# HAT_controller.net
KiCad netlist of a schematic drawn in Altium Designer
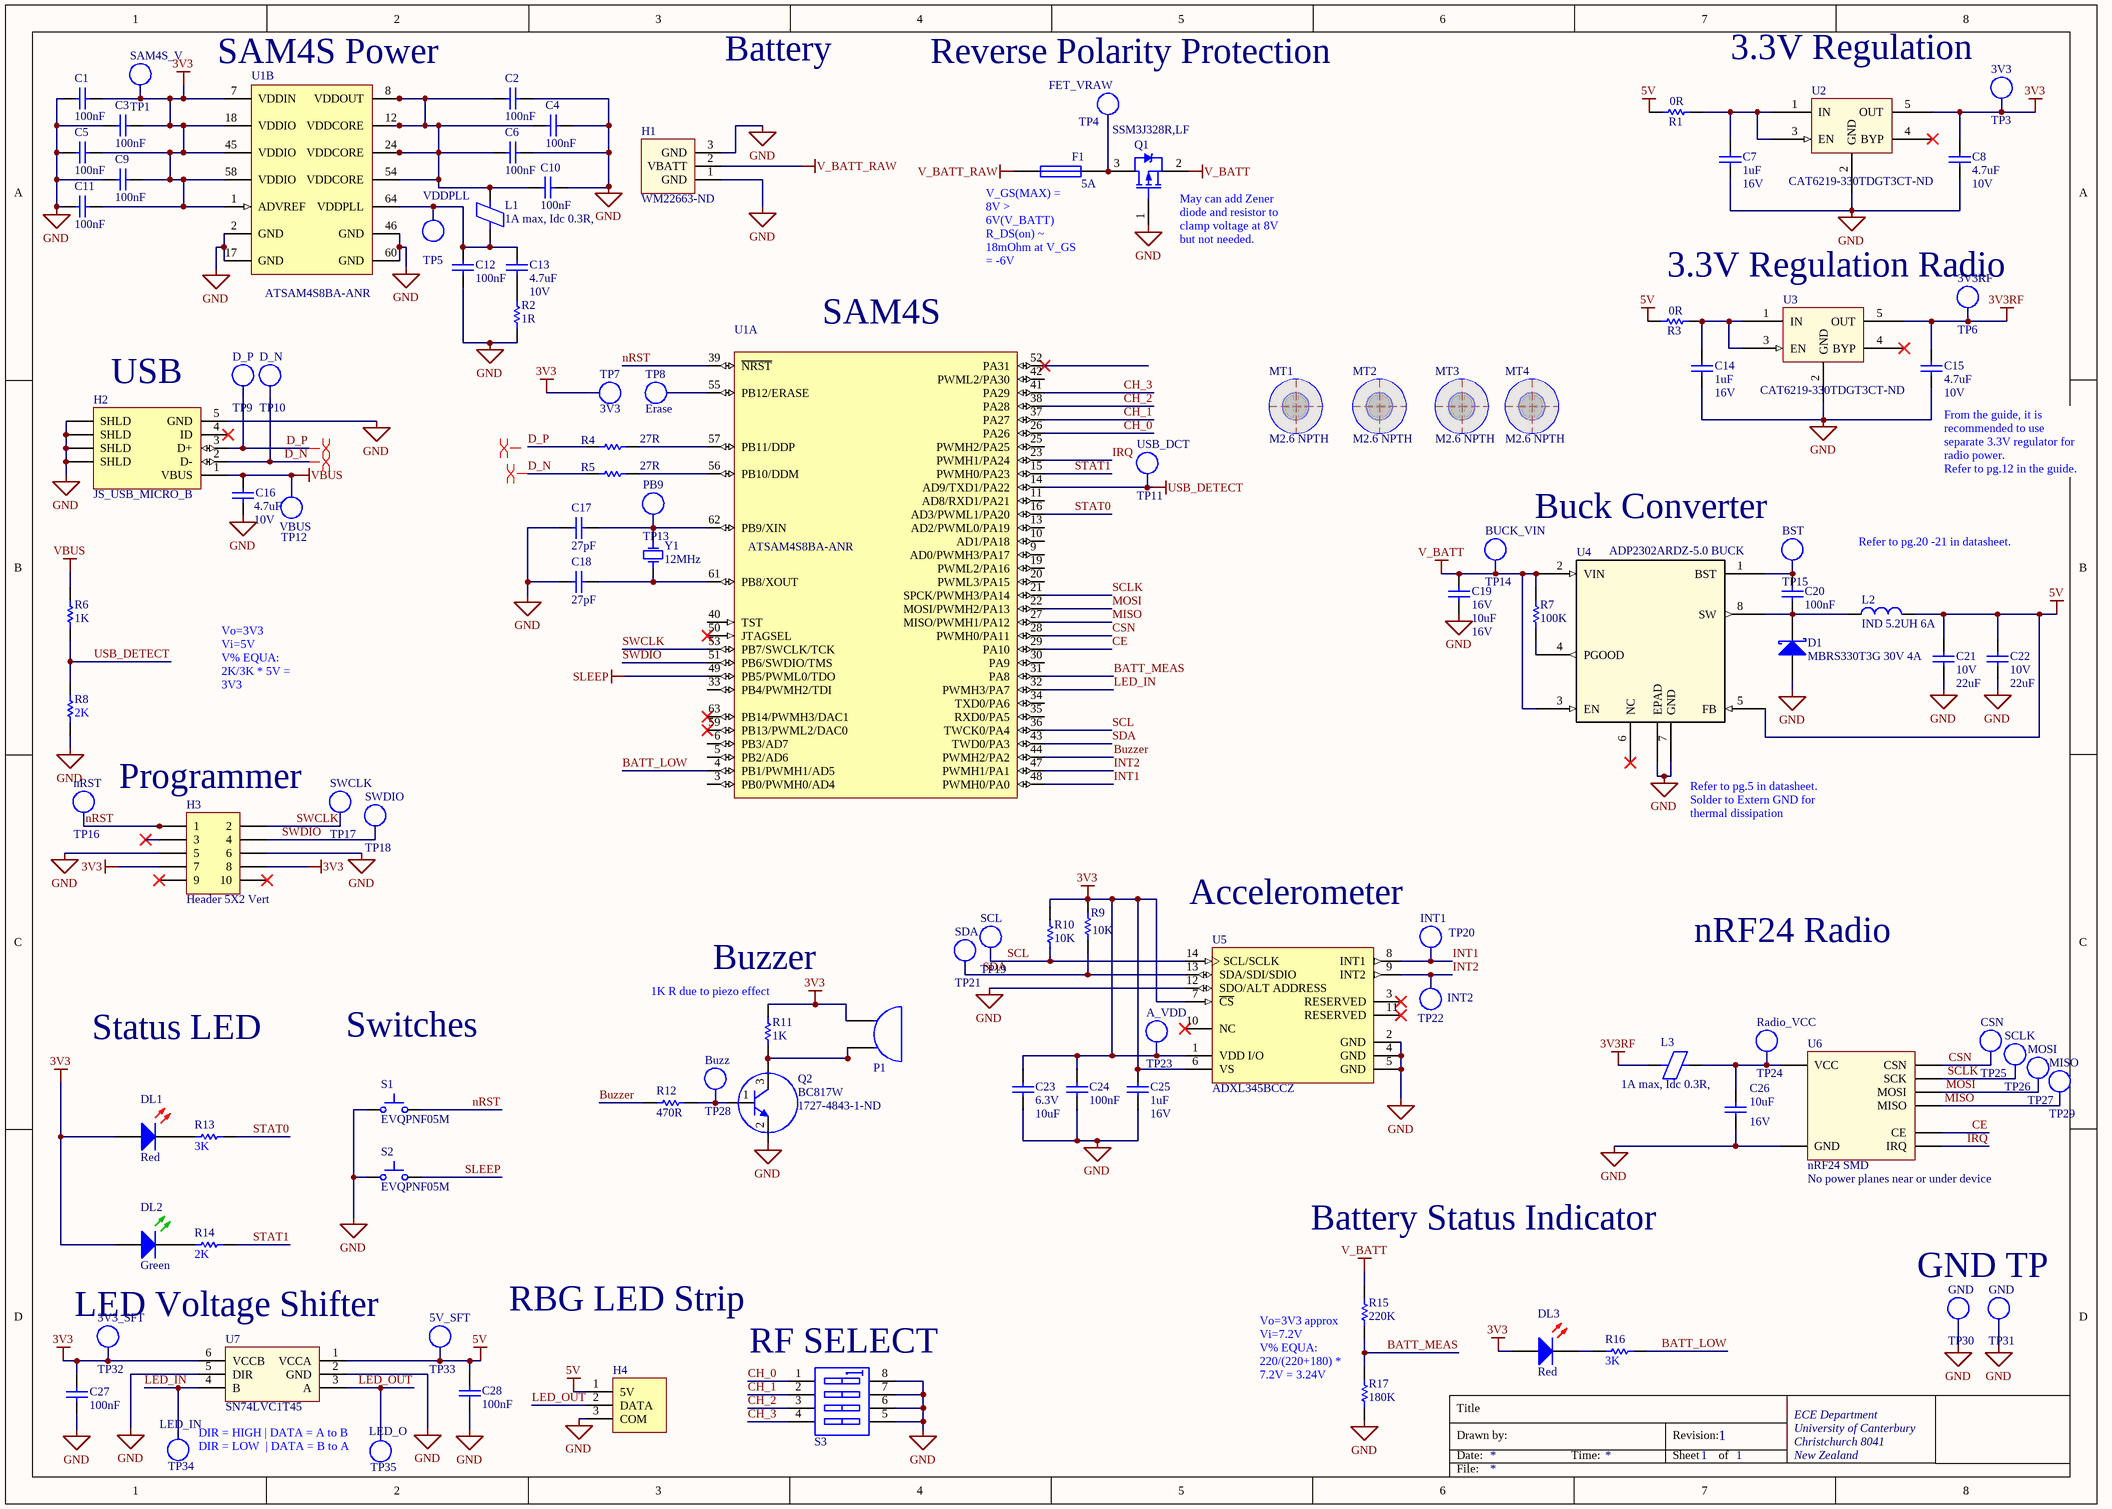
[diagram p0: HAT_controller.SchDoc]

(export (version "E")
  (design (tool "Eeschema 10.0.6"))
  (components
    (comp (ref "C1")
      (value "100nF")
      (footprint "CAPC1608L")
      (description "CAP CER 100nF X7R +-10% 50V 0603")
      (libsource (lib "ECE_ComponentsAD23") (part "CC_100nF_0603"))
    )
    (comp (ref "C2")
      (value "100nF")
      (footprint "CAPC1608L")
      (description "CAP CER 100nF X7R +-10% 50V 0603")
      (libsource (lib "ECE_ComponentsAD23") (part "CC_100nF_0603"))
    )
    (comp (ref "C3")
      (value "100nF")
      (footprint "CAPC1608L")
      (description "CAP CER 100nF X7R +-10% 50V 0603")
      (libsource (lib "ECE_ComponentsAD23") (part "CC_100nF_0603"))
    )
    (comp (ref "C4")
      (value "100nF")
      (footprint "CAPC1608L")
      (description "CAP CER 100nF X7R +-10% 50V 0603")
      (libsource (lib "ECE_ComponentsAD23") (part "CC_100nF_0603"))
    )
    (comp (ref "C5")
      (value "100nF")
      (footprint "CAPC1608L")
      (description "CAP CER 100nF X7R +-10% 50V 0603")
      (libsource (lib "ECE_ComponentsAD23") (part "CC_100nF_0603"))
    )
    (comp (ref "C6")
      (value "100nF")
      (footprint "CAPC1608L")
      (description "CAP CER 100nF X7R +-10% 50V 0603")
      (libsource (lib "ECE_ComponentsAD23") (part "CC_100nF_0603"))
    )
    (comp (ref "C7")
      (value "1uF")
      (footprint "CAPC1608L")
      (description "CAP CER 1uF Y5V -20% +80% 16V 0603")
      (fields (field (name "MAX VOLTAGE") "16V"))
      (libsource (lib "ECE_ComponentsAD23") (part "CC_1uF_0603"))
    )
    (comp (ref "C8")
      (value "4.7uF")
      (footprint "CAPC1608N")
      (description "CAP CER 4.7uF X5R +-20%  10V 0603")
      (fields (field (name "MAX VOLTAGE") "10V"))
      (libsource (lib "ECE_ComponentsAD23") (part "CC_4.7uF_0603"))
    )
    (comp (ref "C9")
      (value "100nF")
      (footprint "CAPC1608L")
      (description "CAP CER 100nF X7R +-10% 50V 0603")
      (libsource (lib "ECE_ComponentsAD23") (part "CC_100nF_0603"))
    )
    (comp (ref "C10")
      (value "100nF")
      (footprint "CAPC1608L")
      (description "CAP CER 100nF X7R +-10% 50V 0603")
      (libsource (lib "ECE_ComponentsAD23") (part "CC_100nF_0603"))
    )
    (comp (ref "C11")
      (value "100nF")
      (footprint "CAPC1608L")
      (description "CAP CER 100nF X7R +-10% 50V 0603")
      (libsource (lib "ECE_ComponentsAD23") (part "CC_100nF_0603"))
    )
    (comp (ref "C12")
      (value "100nF")
      (footprint "CAPC1608L")
      (description "CAP CER 100nF X7R +-10% 50V 0603")
      (libsource (lib "ECE_ComponentsAD23") (part "CC_100nF_0603"))
    )
    (comp (ref "C13")
      (value "4.7uF")
      (footprint "CAPC1608N")
      (description "CAP CER 4.7uF X5R +-20%  10V 0603")
      (fields (field (name "MAX VOLTAGE") "10V"))
      (libsource (lib "ECE_ComponentsAD23") (part "CC_4.7uF_0603"))
    )
    (comp (ref "C14")
      (value "1uF")
      (footprint "CAPC1608L")
      (description "CAP CER 1uF Y5V -20% +80% 16V 0603")
      (fields (field (name "MAX VOLTAGE") "16V"))
      (libsource (lib "ECE_ComponentsAD23") (part "CC_1uF_0603"))
    )
    (comp (ref "C15")
      (value "4.7uF")
      (footprint "CAPC1608N")
      (description "CAP CER 4.7uF X5R +-20%  10V 0603")
      (fields (field (name "MAX VOLTAGE") "10V"))
      (libsource (lib "ECE_ComponentsAD23") (part "CC_4.7uF_0603"))
    )
    (comp (ref "C16")
      (value "4.7uF")
      (footprint "CAPC1608N")
      (description "CAP CER 4.7uF X5R +-20%  10V 0603")
      (fields (field (name "MAX VOLTAGE") "10V"))
      (libsource (lib "ECE_ComponentsAD23") (part "CC_4.7uF_0603"))
    )
    (comp (ref "C17")
      (value "27pF")
      (footprint "CAPC1608L")
      (description "CAP CER 27pF NPO/COG +-5% 50V 0603")
      (libsource (lib "ECE_ComponentsAD23") (part "CC_27pF_0603"))
    )
    (comp (ref "C18")
      (value "27pF")
      (footprint "CAPC1608L")
      (description "CAP CER 27pF NPO/COG +-5% 50V 0603")
      (libsource (lib "ECE_ComponentsAD23") (part "CC_27pF_0603"))
    )
    (comp (ref "C19")
      (value "10uF")
      (footprint "CAPC2012L")
      (description "CAP CER 10uF X5R 16V 0805")
      (fields
        (field (name "MANUFACTURER") "Samsung Electro-Mechanics")
        (field (name "MANUFACTURER PART NUMBER") "CL21A106KOQNNWE")
        (field (name "VOLTAGE - RATED") "16V")
        (field (name "MAX VOLTAGE") "16V")
      )
      (libsource (lib "ECE_ComponentsAD23") (part "CC_10uF_0805_16V"))
    )
    (comp (ref "C20")
      (value "100nF")
      (footprint "CAPC1608L")
      (description "CAP CER 100nF X7R +-10% 50V 0603")
      (libsource (lib "ECE_ComponentsAD23") (part "CC_100nF_0603"))
    )
    (comp (ref "C21")
      (value "22uF")
      (footprint "CAPC3216L")
      (description "CAP CER 22uF Y5V -20% +80% 10V 1206")
      (fields (field (name "MAX VOLTAGE") "10V"))
      (libsource (lib "ECE_ComponentsAD23") (part "CC_22uF_1206"))
    )
    (comp (ref "C22")
      (value "22uF")
      (footprint "CAPC3216L")
      (description "CAP CER 22uF Y5V -20% +80% 10V 1206")
      (fields (field (name "MAX VOLTAGE") "10V"))
      (libsource (lib "ECE_ComponentsAD23") (part "CC_22uF_1206"))
    )
    (comp (ref "C23")
      (value "10uF")
      (footprint "CAPC1608L")
      (description "CAP CER 10UF X5R +-20% 6V3 0603")
      (fields (field (name "VOLTAGE - RATED") "6.3V"))
      (libsource (lib "ECE_ComponentsAD23") (part "CC_10uF_0603"))
    )
    (comp (ref "C24")
      (value "100nF")
      (footprint "CAPC1608L")
      (description "CAP CER 100nF X7R +-10% 50V 0603")
      (libsource (lib "ECE_ComponentsAD23") (part "CC_100nF_0603"))
    )
    (comp (ref "C25")
      (value "1uF")
      (footprint "CAPC1608L")
      (description "CAP CER 1uF Y5V -20% +80% 16V 0603")
      (fields (field (name "MAX VOLTAGE") "16V"))
      (libsource (lib "ECE_ComponentsAD23") (part "CC_1uF_0603"))
    )
    (comp (ref "C26")
      (value "10uF")
      (footprint "CAPC2012L")
      (description "CAP CER 10uF X5R 16V 0805")
      (fields
        (field (name "MANUFACTURER") "Samsung Electro-Mechanics")
        (field (name "MANUFACTURER PART NUMBER") "CL21A106KOQNNWE")
        (field (name "VOLTAGE - RATED") "16V")
      )
      (libsource (lib "ECE_ComponentsAD23") (part "CC_10uF_0805_16V"))
    )
    (comp (ref "C27")
      (value "100nF")
      (footprint "CAPC1608L")
      (description "CAP CER 100nF X7R +-10% 50V 0603")
      (libsource (lib "ECE_ComponentsAD23") (part "CC_100nF_0603"))
    )
    (comp (ref "C28")
      (value "100nF")
      (footprint "CAPC1608L")
      (description "CAP CER 100nF X7R +-10% 50V 0603")
      (libsource (lib "ECE_ComponentsAD23") (part "CC_100nF_0603"))
    )
    (comp (ref "D1")
      (value "MBRS330T3G 30V 4A")
      (footprint "SMC")
      (description "SCHOTTKY  30V 4A")
      (fields
        (field (name "MANUFACTURER") "ON Semiconductor")
        (field (name "MANUFACTURER PART NUMBER") "MBRS330T3G")
      )
      (libsource (lib "ENCE461AD23") (part "MBRS330T3G"))
    )
    (comp (ref "DL1")
      (value "Red")
      (footprint "WL-SMCW0603")
      (description "LED Red 250mcd 0603 SMD")
      (fields
        (field (name "MANUFACTURER") "WURTH ELEKTRONIK")
        (field (name "MANUFACTURER PART NUMBER") "150060RS75000")
        (field (name "LED COLOUR") "Red")
      )
      (libsource (lib "ECE_ComponentsAD23") (part "DL_150060RS75000"))
    )
    (comp (ref "DL2")
      (value "Green")
      (footprint "WL-SMCW0603")
      (description "LED Green 430mcd 0603 SMD")
      (fields
        (field (name "MANUFACTURER") "WURTH ELEKTRONIK")
        (field (name "MANUFACTURER PART NUMBER") "150060GS75000")
        (field (name "LED COLOUR") "Green")
      )
      (libsource (lib "ECE_ComponentsAD23") (part "DL_150060GS75000"))
    )
    (comp (ref "DL3")
      (value "Red")
      (footprint "WL-SMCW0603")
      (description "LED Red 250mcd 0603 SMD")
      (fields
        (field (name "MANUFACTURER") "WURTH ELEKTRONIK")
        (field (name "MANUFACTURER PART NUMBER") "150060RS75000")
        (field (name "LED COLOUR") "Red")
      )
      (libsource (lib "ECE_ComponentsAD23") (part "DL_150060RS75000"))
    )
    (comp (ref "F1")
      (value "5A")
      (footprint "RESC3216N")
      (description "Fuse 5.0A Fast Acting 1206 SMD")
      (fields (field (name "MANUFACTURER PART NUMBER") "C1F5") (field (name "MANUFACTURER") "Bel TRP"))
      (libsource (lib "ECE_ComponentsAD23") (part "FS_Fuse_5.0A"))
    )
    (comp (ref "H1")
      (value "Battery_HEADER_3pin")
      (footprint "BATT_HEADER_3POS")
      (description "3Pin Header 2.54mm spacing\r\nDigikey #WM22663-ND")
      (fields (field (name "SUPPLIER PART NUMBER 1") "WM22663-ND"))
      (libsource (lib "ENCE461AD23") (part "Battery_HEADER_3pin"))
    )
    (comp (ref "H2")
      (value "JS_USB_MICRO_B")
      (footprint "FCI_USB_10118194-0001LF")
      (description "CONN USB MICRO B RECPT SMT R/A")
      (fields (field (name "MANUFACTURER") "FCI") (field (name "MANUFACTURER PART NUMBER") "10118194-0001LF"))
      (libsource (lib "ECE_ComponentsAD23") (part "JS_USB_MICRO_B_SMT"))
    )
    (comp (ref "H3")
      (value "Header 5X2 Vert")
      (footprint "IDC2.54-V10D")
      (description "IDC Header, 2,54mm, 10-Pin, Vert")
      (libsource (lib "ECE_ComponentsAD23") (part "JA_HDR_IDC_5X2_VERT"))
    )
    (comp (ref "H4")
      (value "3 Pin Molex KK Hdr")
      (footprint "MOLEX_KK_3_HDR")
      (description "CONN HEADER 3POS 2.54mm VERT_Thru Hole")
      (fields (field (name "MANUFACTURER") "Molex"))
      (libsource (lib "ENCE461AD23") (part "LED_Strip_Header"))
    )
    (comp (ref "L1")
      (value "1A max, Idc 0.3R,")
      (footprint "INDC3216L")
      (description "Ferrite Bead, Rdc 0.3R, Z100MHZ 600R, Imax 1A, SMD 1206")
      (fields
        (field (name "MANUFACTURER") "FAIR-RITE")
        (field (name "MANUFACTURER PART NUMBER") "2512066017Y1")
      )
      (libsource (lib "ECE_ComponentsAD23") (part "IN_Ferrite-Bead"))
    )
    (comp (ref "L2")
      (value "IND 5.2UH 6A")
      (footprint "INDUCTOR5u2")
      (description "FIXED IND 5.2UH 6A 22 MOHM SMD")
      (fields
        (field (name "MANUFACTURER") "Sumida America Components Inc.")
        (field (name "MANUFACTURER PART NUMBER") "CDRH104RNP-5R2NC")
      )
      (libsource (lib "ENCE461AD23") (part "CDRH104RNP-5R2NC"))
    )
    (comp (ref "L3")
      (value "1A max, Idc 0.3R,")
      (footprint "INDC3216L")
      (description "Ferrite Bead, Rdc 0.3R, Z100MHZ 600R, Imax 1A, SMD 1206")
      (fields
        (field (name "MANUFACTURER") "FAIR-RITE")
        (field (name "MANUFACTURER PART NUMBER") "2512066017Y1")
      )
      (libsource (lib "ECE_ComponentsAD23") (part "IN_Ferrite-Bead"))
    )
    (comp (ref "MT1")
      (value "M2.6 NPTH")
      (footprint "MNT-HOLE_2.6mm_NPTH")
      (description "Fixing M2.6 Mount Hole NPTH")
      (fields (field (name "MANUFACTURER") "Hi-Q"))
      (libsource (lib "ECE_ComponentsAD23") (part "MC_M2.6_HOLE"))
    )
    (comp (ref "MT2")
      (value "M2.6 NPTH")
      (footprint "MNT-HOLE_2.6mm_NPTH")
      (description "Fixing M2.6 Mount Hole NPTH")
      (fields (field (name "MANUFACTURER") "Hi-Q"))
      (libsource (lib "ECE_ComponentsAD23") (part "MC_M2.6_HOLE"))
    )
    (comp (ref "MT3")
      (value "M2.6 NPTH")
      (footprint "MNT-HOLE_2.6mm_NPTH")
      (description "Fixing M2.6 Mount Hole NPTH")
      (fields (field (name "MANUFACTURER") "Hi-Q"))
      (libsource (lib "ECE_ComponentsAD23") (part "MC_M2.6_HOLE"))
    )
    (comp (ref "MT4")
      (value "M2.6 NPTH")
      (footprint "MNT-HOLE_2.6mm_NPTH")
      (description "Fixing M2.6 Mount Hole NPTH")
      (fields (field (name "MANUFACTURER") "Hi-Q"))
      (libsource (lib "ECE_ComponentsAD23") (part "MC_M2.6_HOLE"))
    )
    (comp (ref "P1")
      (value "Piezo Buzzer")
      (footprint "BUZZER")
      (description "TDK - PS1240P02BT - BUZZER, PIEZO, 70DB, 12.2MM")
      (libsource (lib "ENCE461AD23") (part "Piezo Buzzer"))
    )
    (comp (ref "Q1")
      (value "SSM3J328R,LF")
      (footprint "SOT23_L")
      (description "MOSFET P-CH 20V 6A SOT23-3")
      (fields
        (field (name "MANUFACTURER") "Toshiba")
        (field (name "MANUFACTURER PART NUMBER") "SSM3J328R,LF")
      )
      (libsource (lib "ECE_ComponentsAD23") (part "TM_SSM3J328R"))
    )
    (comp (ref "Q2")
      (value "BC817W")
      (footprint "SOT323_M")
      (description "NPN GP Bipolar Transistor 45V 500mA SOT323")
      (fields (field (name "MANUFACTURER") "NXP") (field (name "SUPPLIER PART NUMBER 2") "1727-4843-1-ND"))
      (libsource (lib "ECE_ComponentsAD23") (part "TB_BC817W"))
    )
    (comp (ref "R1")
      (value "0R")
      (footprint "RESC1608L")
      (description "RES 0.0 OHM 1/10W 5% 0603 SMD")
      (libsource (lib "ECE_ComponentsAD23") (part "RS_0R0"))
    )
    (comp (ref "R2")
      (value "1R")
      (footprint "RESC3216L")
      (description "RES 1R OHM 1/4W 5% 1206 SMD")
      (libsource (lib "ECE_ComponentsAD23") (part "RT_1R"))
    )
    (comp (ref "R3")
      (value "0R")
      (footprint "RESC1608L")
      (description "RES 0.0 OHM 1/10W 5% 0603 SMD")
      (libsource (lib "ECE_ComponentsAD23") (part "RS_0R0"))
    )
    (comp (ref "R4")
      (value "27R")
      (footprint "RESC1608L")
      (description "RES 27 OHM 1/10W 5% 0603 SMD")
      (libsource (lib "ECE_ComponentsAD23") (part "RS_27R"))
    )
    (comp (ref "R5")
      (value "27R")
      (footprint "RESC1608L")
      (description "RES 27 OHM 1/10W 5% 0603 SMD")
      (libsource (lib "ECE_ComponentsAD23") (part "RS_27R"))
    )
    (comp (ref "R6")
      (value "1K")
      (footprint "RESC1608L")
      (description "RES 1.0K OHM 1/10W 5% 0603 SMD")
      (libsource (lib "ECE_ComponentsAD23") (part "RS_1K"))
    )
    (comp (ref "R7")
      (value "100K")
      (footprint "RESC1608L")
      (description "RES 100K OHM 1/10W 5% 0603 SMD")
      (libsource (lib "ECE_ComponentsAD23") (part "RS_100K"))
    )
    (comp (ref "R8")
      (value "2K")
      (footprint "RESC1608L")
      (description "RES 2K OHM 1/10W 5% 0603 SMD")
      (libsource (lib "ECE_ComponentsAD23") (part "RS_2K"))
    )
    (comp (ref "R9")
      (value "10K")
      (footprint "RESC1608L")
      (description "RES 10.0K OHM 1/10W 5% 0603 SMD")
      (libsource (lib "ECE_ComponentsAD23") (part "RS_10K"))
    )
    (comp (ref "R10")
      (value "10K")
      (footprint "RESC1608L")
      (description "RES 10.0K OHM 1/10W 5% 0603 SMD")
      (libsource (lib "ECE_ComponentsAD23") (part "RS_10K"))
    )
    (comp (ref "R11")
      (value "1K")
      (footprint "RESC1608L")
      (description "RES 1.0K OHM 1/10W 5% 0603 SMD")
      (libsource (lib "ECE_ComponentsAD23") (part "RS_1K"))
    )
    (comp (ref "R12")
      (value "470R")
      (footprint "RESC1608L")
      (description "RES 470 OHM 1/10W 5% 0603 SMD")
      (libsource (lib "ECE_ComponentsAD23") (part "RS_470R"))
    )
    (comp (ref "R13")
      (value "3K")
      (footprint "RESC1608L")
      (description "RES 3K OHM 1/10W 5% 0603 SMD")
      (libsource (lib "ECE_ComponentsAD23") (part "RS_3K"))
    )
    (comp (ref "R14")
      (value "2K")
      (footprint "RESC1608L")
      (description "RES 2K OHM 1/10W 5% 0603 SMD")
      (libsource (lib "ECE_ComponentsAD23") (part "RS_2K"))
    )
    (comp (ref "R15")
      (value "220K")
      (footprint "RESC1608L")
      (description "RES 3.3K OHM 1/10W 5% 0603 SMD")
      (libsource (lib "ECE_ComponentsAD23") (part "RS_220K"))
    )
    (comp (ref "R16")
      (value "3K")
      (footprint "RESC1608L")
      (description "RES 3K OHM 1/10W 5% 0603 SMD")
      (libsource (lib "ECE_ComponentsAD23") (part "RS_3K"))
    )
    (comp (ref "R17")
      (value "180K")
      (footprint "RESC1608L")
      (description "RES 180K OHM 1/10W 5% 0603 SMD")
      (libsource (lib "ECE_ComponentsAD23") (part "RS_180K"))
    )
    (comp (ref "S1")
      (value "EVQPNF05M")
      (footprint "EVQPNF05M")
      (description "Panasonic 6 x 3.5mm SMD Light Touch Switch Type SMD")
      (fields (field (name "MANUFACTURER") "Panasonic"))
      (libsource (lib "ECE_ComponentsAD23") (part "WS_EVQPNF05M"))
    )
    (comp (ref "S2")
      (value "EVQPNF05M")
      (footprint "EVQPNF05M")
      (description "Panasonic 6 x 3.5mm SMD Light Touch Switch Type SMD")
      (fields (field (name "MANUFACTURER") "Panasonic"))
      (libsource (lib "ECE_ComponentsAD23") (part "WS_EVQPNF05M"))
    )
    (comp (ref "S3")
      (value "WS_SW DIP-4")
      (footprint "DIP_SW_4WAY_SMD -")
      (description "DIP Switch, 4 Position, SPST SMD")
      (fields
        (field (name "MANUFACTURER") "OMRON ELECTRONIC COMPONENTS")
        (field (name "MANUFACTURER PART NUMBER") "A6SN-4101")
      )
      (libsource (lib "ECE_ComponentsAD23") (part "WS_SW DIP-4"))
    )
    (comp (ref "TP1")
      (value "SAM4S_V")
      (footprint "TP_0603")
      (description "Test Point 1.65X0.9X1.2mm SMD")
      (fields
        (field (name "MANUFACTURER") "TE Connectivity AMP Connectors")
        (field (name "MANUFACTURER PART NUMBER") "1625854-3")
      )
      (libsource (lib "ECE_ComponentsAD23") (part "TP_0603"))
    )
    (comp (ref "TP3")
      (value "3V3")
      (footprint "TP_0603")
      (description "Test Point 1.65X0.9X1.2mm SMD")
      (fields
        (field (name "MANUFACTURER") "TE Connectivity AMP Connectors")
        (field (name "MANUFACTURER PART NUMBER") "1625854-3")
      )
      (libsource (lib "ECE_ComponentsAD23") (part "TP_0603"))
    )
    (comp (ref "TP4")
      (value "FET_VRAW")
      (footprint "TP_0603")
      (description "Test Point 1.65X0.9X1.2mm SMD")
      (fields
        (field (name "MANUFACTURER") "TE Connectivity AMP Connectors")
        (field (name "MANUFACTURER PART NUMBER") "1625854-3")
      )
      (libsource (lib "ECE_ComponentsAD23") (part "TP_0603"))
    )
    (comp (ref "TP5")
      (value "VDDPLL")
      (footprint "TP_0603")
      (description "Test Point 1.65X0.9X1.2mm SMD")
      (fields
        (field (name "MANUFACTURER") "TE Connectivity AMP Connectors")
        (field (name "MANUFACTURER PART NUMBER") "1625854-3")
      )
      (libsource (lib "ECE_ComponentsAD23") (part "TP_0603"))
    )
    (comp (ref "TP6")
      (value "3V3RF")
      (footprint "TP_0603")
      (description "Test Point 1.65X0.9X1.2mm SMD")
      (fields
        (field (name "MANUFACTURER") "TE Connectivity AMP Connectors")
        (field (name "MANUFACTURER PART NUMBER") "1625854-3")
      )
      (libsource (lib "ECE_ComponentsAD23") (part "TP_0603"))
    )
    (comp (ref "TP7")
      (value "3V3")
      (footprint "TP_0603")
      (description "Test Point 1.65X0.9X1.2mm SMD")
      (fields
        (field (name "MANUFACTURER") "TE Connectivity AMP Connectors")
        (field (name "MANUFACTURER PART NUMBER") "1625854-3")
      )
      (libsource (lib "ECE_ComponentsAD23") (part "TP_0603"))
    )
    (comp (ref "TP8")
      (value "Erase")
      (footprint "TP_0603")
      (description "Test Point 1.65X0.9X1.2mm SMD")
      (fields
        (field (name "MANUFACTURER") "TE Connectivity AMP Connectors")
        (field (name "MANUFACTURER PART NUMBER") "1625854-3")
      )
      (libsource (lib "ECE_ComponentsAD23") (part "TP_0603"))
    )
    (comp (ref "TP9")
      (value "D_P")
      (footprint "TP_0603")
      (description "Test Point 1.65X0.9X1.2mm SMD")
      (fields
        (field (name "MANUFACTURER") "TE Connectivity AMP Connectors")
        (field (name "MANUFACTURER PART NUMBER") "1625854-3")
      )
      (libsource (lib "ECE_ComponentsAD23") (part "TP_0603"))
    )
    (comp (ref "TP10")
      (value "D_N")
      (footprint "TP_0603")
      (description "Test Point 1.65X0.9X1.2mm SMD")
      (fields
        (field (name "MANUFACTURER") "TE Connectivity AMP Connectors")
        (field (name "MANUFACTURER PART NUMBER") "1625854-3")
      )
      (libsource (lib "ECE_ComponentsAD23") (part "TP_0603"))
    )
    (comp (ref "TP11")
      (value "USB_DCT")
      (footprint "TP_0603")
      (description "Test Point 1.65X0.9X1.2mm SMD")
      (fields
        (field (name "MANUFACTURER") "TE Connectivity AMP Connectors")
        (field (name "MANUFACTURER PART NUMBER") "1625854-3")
      )
      (libsource (lib "ECE_ComponentsAD23") (part "TP_0603"))
    )
    (comp (ref "TP12")
      (value "VBUS")
      (footprint "TP_0603")
      (description "Test Point 1.65X0.9X1.2mm SMD")
      (fields
        (field (name "MANUFACTURER") "TE Connectivity AMP Connectors")
        (field (name "MANUFACTURER PART NUMBER") "1625854-3")
      )
      (libsource (lib "ECE_ComponentsAD23") (part "TP_0603"))
    )
    (comp (ref "TP13")
      (value "PB9")
      (footprint "TP_0603")
      (description "Test Point 1.65X0.9X1.2mm SMD")
      (fields
        (field (name "MANUFACTURER") "TE Connectivity AMP Connectors")
        (field (name "MANUFACTURER PART NUMBER") "1625854-3")
      )
      (libsource (lib "ECE_ComponentsAD23") (part "TP_0603"))
    )
    (comp (ref "TP14")
      (value "BUCK_VIN")
      (footprint "TP_0603")
      (description "Test Point 1.65X0.9X1.2mm SMD")
      (fields
        (field (name "MANUFACTURER") "TE Connectivity AMP Connectors")
        (field (name "MANUFACTURER PART NUMBER") "1625854-3")
      )
      (libsource (lib "ECE_ComponentsAD23") (part "TP_0603"))
    )
    (comp (ref "TP15")
      (value "BST")
      (footprint "TP_0603")
      (description "Test Point 1.65X0.9X1.2mm SMD")
      (fields
        (field (name "MANUFACTURER") "TE Connectivity AMP Connectors")
        (field (name "MANUFACTURER PART NUMBER") "1625854-3")
      )
      (libsource (lib "ECE_ComponentsAD23") (part "TP_0603"))
    )
    (comp (ref "TP16")
      (value "nRST")
      (footprint "TP_0603")
      (description "Test Point 1.65X0.9X1.2mm SMD")
      (fields
        (field (name "MANUFACTURER") "TE Connectivity AMP Connectors")
        (field (name "MANUFACTURER PART NUMBER") "1625854-3")
      )
      (libsource (lib "ECE_ComponentsAD23") (part "TP_0603"))
    )
    (comp (ref "TP17")
      (value "SWCLK")
      (footprint "TP_0603")
      (description "Test Point 1.65X0.9X1.2mm SMD")
      (fields
        (field (name "MANUFACTURER") "TE Connectivity AMP Connectors")
        (field (name "MANUFACTURER PART NUMBER") "1625854-3")
      )
      (libsource (lib "ECE_ComponentsAD23") (part "TP_0603"))
    )
    (comp (ref "TP18")
      (value "SWDIO")
      (footprint "TP_0603")
      (description "Test Point 1.65X0.9X1.2mm SMD")
      (fields
        (field (name "MANUFACTURER") "TE Connectivity AMP Connectors")
        (field (name "MANUFACTURER PART NUMBER") "1625854-3")
      )
      (libsource (lib "ECE_ComponentsAD23") (part "TP_0603"))
    )
    (comp (ref "TP19")
      (value "SCL")
      (footprint "TP_0603")
      (description "Test Point 1.65X0.9X1.2mm SMD")
      (fields
        (field (name "MANUFACTURER") "TE Connectivity AMP Connectors")
        (field (name "MANUFACTURER PART NUMBER") "1625854-3")
      )
      (libsource (lib "ECE_ComponentsAD23") (part "TP_0603"))
    )
    (comp (ref "TP20")
      (value "INT1")
      (footprint "TP_0603")
      (description "Test Point 1.65X0.9X1.2mm SMD")
      (fields
        (field (name "MANUFACTURER") "TE Connectivity AMP Connectors")
        (field (name "MANUFACTURER PART NUMBER") "1625854-3")
      )
      (libsource (lib "ECE_ComponentsAD23") (part "TP_0603"))
    )
    (comp (ref "TP21")
      (value "SDA")
      (footprint "TP_0603")
      (description "Test Point 1.65X0.9X1.2mm SMD")
      (fields
        (field (name "MANUFACTURER") "TE Connectivity AMP Connectors")
        (field (name "MANUFACTURER PART NUMBER") "1625854-3")
      )
      (libsource (lib "ECE_ComponentsAD23") (part "TP_0603"))
    )
    (comp (ref "TP22")
      (value "INT2")
      (footprint "TP_0603")
      (description "Test Point 1.65X0.9X1.2mm SMD")
      (fields
        (field (name "MANUFACTURER") "TE Connectivity AMP Connectors")
        (field (name "MANUFACTURER PART NUMBER") "1625854-3")
      )
      (libsource (lib "ECE_ComponentsAD23") (part "TP_0603"))
    )
    (comp (ref "TP23")
      (value "A_VDD")
      (footprint "TP_0603")
      (description "Test Point 1.65X0.9X1.2mm SMD")
      (fields
        (field (name "MANUFACTURER") "TE Connectivity AMP Connectors")
        (field (name "MANUFACTURER PART NUMBER") "1625854-3")
      )
      (libsource (lib "ECE_ComponentsAD23") (part "TP_0603"))
    )
    (comp (ref "TP24")
      (value "Radio_VCC")
      (footprint "TP_0603")
      (description "Test Point 1.65X0.9X1.2mm SMD")
      (fields
        (field (name "MANUFACTURER") "TE Connectivity AMP Connectors")
        (field (name "MANUFACTURER PART NUMBER") "1625854-3")
      )
      (libsource (lib "ECE_ComponentsAD23") (part "TP_0603"))
    )
    (comp (ref "TP25")
      (value "CSN")
      (footprint "TP_0603")
      (description "Test Point 1.65X0.9X1.2mm SMD")
      (fields
        (field (name "MANUFACTURER") "TE Connectivity AMP Connectors")
        (field (name "MANUFACTURER PART NUMBER") "1625854-3")
      )
      (libsource (lib "ECE_ComponentsAD23") (part "TP_0603"))
    )
    (comp (ref "TP26")
      (value "SCLK")
      (footprint "TP_0603")
      (description "Test Point 1.65X0.9X1.2mm SMD")
      (fields
        (field (name "MANUFACTURER") "TE Connectivity AMP Connectors")
        (field (name "MANUFACTURER PART NUMBER") "1625854-3")
      )
      (libsource (lib "ECE_ComponentsAD23") (part "TP_0603"))
    )
    (comp (ref "TP27")
      (value "MOSI")
      (footprint "TP_0603")
      (description "Test Point 1.65X0.9X1.2mm SMD")
      (fields
        (field (name "MANUFACTURER") "TE Connectivity AMP Connectors")
        (field (name "MANUFACTURER PART NUMBER") "1625854-3")
      )
      (libsource (lib "ECE_ComponentsAD23") (part "TP_0603"))
    )
    (comp (ref "TP28")
      (value "Buzz")
      (footprint "TP_0603")
      (description "Test Point 1.65X0.9X1.2mm SMD")
      (fields
        (field (name "MANUFACTURER") "TE Connectivity AMP Connectors")
        (field (name "MANUFACTURER PART NUMBER") "1625854-3")
      )
      (libsource (lib "ECE_ComponentsAD23") (part "TP_0603"))
    )
    (comp (ref "TP29")
      (value "MISO")
      (footprint "TP_0603")
      (description "Test Point 1.65X0.9X1.2mm SMD")
      (fields
        (field (name "MANUFACTURER") "TE Connectivity AMP Connectors")
        (field (name "MANUFACTURER PART NUMBER") "1625854-3")
      )
      (libsource (lib "ECE_ComponentsAD23") (part "TP_0603"))
    )
    (comp (ref "TP30")
      (value "GND")
      (footprint "TP_0603")
      (description "Test Point 1.65X0.9X1.2mm SMD")
      (fields
        (field (name "MANUFACTURER") "TE Connectivity AMP Connectors")
        (field (name "MANUFACTURER PART NUMBER") "1625854-3")
      )
      (libsource (lib "ECE_ComponentsAD23") (part "TP_0603"))
    )
    (comp (ref "TP31")
      (value "GND")
      (footprint "TP_0603")
      (description "Test Point 1.65X0.9X1.2mm SMD")
      (fields
        (field (name "MANUFACTURER") "TE Connectivity AMP Connectors")
        (field (name "MANUFACTURER PART NUMBER") "1625854-3")
      )
      (libsource (lib "ECE_ComponentsAD23") (part "TP_0603"))
    )
    (comp (ref "TP32")
      (value "3V3_SFT")
      (footprint "TP_0603")
      (description "Test Point 1.65X0.9X1.2mm SMD")
      (fields
        (field (name "MANUFACTURER") "TE Connectivity AMP Connectors")
        (field (name "MANUFACTURER PART NUMBER") "1625854-3")
      )
      (libsource (lib "ECE_ComponentsAD23") (part "TP_0603"))
    )
    (comp (ref "TP33")
      (value "5V_SFT")
      (footprint "TP_0603")
      (description "Test Point 1.65X0.9X1.2mm SMD")
      (fields
        (field (name "MANUFACTURER") "TE Connectivity AMP Connectors")
        (field (name "MANUFACTURER PART NUMBER") "1625854-3")
      )
      (libsource (lib "ECE_ComponentsAD23") (part "TP_0603"))
    )
    (comp (ref "TP34")
      (value "LED_IN")
      (footprint "TP_0603")
      (description "Test Point 1.65X0.9X1.2mm SMD")
      (fields
        (field (name "MANUFACTURER") "TE Connectivity AMP Connectors")
        (field (name "MANUFACTURER PART NUMBER") "1625854-3")
      )
      (libsource (lib "ECE_ComponentsAD23") (part "TP_0603"))
    )
    (comp (ref "TP35")
      (value "LED_O")
      (footprint "TP_0603")
      (description "Test Point 1.65X0.9X1.2mm SMD")
      (fields
        (field (name "MANUFACTURER") "TE Connectivity AMP Connectors")
        (field (name "MANUFACTURER PART NUMBER") "1625854-3")
      )
      (libsource (lib "ECE_ComponentsAD23") (part "TP_0603"))
    )
    (comp (ref "U1")
      (value "ATSAM4S8BA-ANR")
      (footprint "LQFP64_L")
      (description "IC MCU 32BIT 512KB FLASH 64LQFP")
      (fields (field (name "MANUFACTURER") "Atmel"))
      (libsource (lib "ECE_ComponentsAD23") (part "SE_ATSAM4S16BA-MU"))
    )
    (comp (ref "U2")
      (value "CAT6219-330TDGT3")
      (footprint "SOT95P280X145-5N")
      (description "IC REG LIN 3.3V 500MA TSOT23-5")
      (fields
        (field (name "BASE PART NUMBER") "CAT6219")
        (field (name "SUPPLIER PART NUMBER") "CAT6219-330TDGT3CT-ND")
      )
      (libsource (lib "ENCE461AD23") (part "SV_CAT6219-330TDGT3"))
    )
    (comp (ref "U3")
      (value "CAT6219-330TDGT3")
      (footprint "SOT95P280X145-5N")
      (description "IC REG LIN 3.3V 500MA TSOT23-5")
      (fields
        (field (name "BASE PART NUMBER") "CAT6219")
        (field (name "SUPPLIER PART NUMBER") "CAT6219-330TDGT3CT-ND")
      )
      (libsource (lib "ENCE461AD23") (part "SV_CAT6219-330TDGT3"))
    )
    (comp (ref "U4")
      (value "ADP2302ARDZ-5.0 BUCK")
      (footprint "RD_8_1")
      (description "IC REG BUCK 5V 2A 8SOIC")
      (fields (field (name "MANUFACTURER_PART_NUMBER") "ADP2302ARDZ-5.0-R7"))
      (libsource (lib "ENCE461AD23") (part "ADP2302ARDZ-5.0-R7"))
    )
    (comp (ref "U5")
      (value "ADXL345BCCZ")
      (footprint "ADI-CC-14-1_V")
      (fields (field (name "MANUFACTURER") "Analog Devices"))
      (libsource (lib "ENCE461AD23") (part "ADXL345BCCZ"))
    )
    (comp (ref "U6")
      (value "nRF24 SMD")
      (footprint "NRF24")
      (description "nRF24 SMD Module")
      (fields (field (name "WARNING") "No power planes near or under device"))
      (libsource (lib "ENCE461AD23") (part "NRF24"))
    )
    (comp (ref "U7")
      (value "SN74LVC1T45")
      (footprint "SOT23-6_N")
      (description "1.8V - 5V level converter")
      (libsource (lib "ENCE461AD23") (part "SN74LVC1T45"))
    )
    (comp (ref "Y1")
      (value "12MHz")
      (footprint "6.0X3.5-4")
      (description "CRYSTAL 12MHZ 18PF 6X3.5mm SMD")
      (fields
        (field (name "MANUFACTURER") "CTS-Frequency Controls")
        (field (name "MANUFACTURER PART NUMBER") "406C35D12M00000")
        (field (name "FREQUENCY") "12MHz")
      )
      (libsource (lib "ECE_ComponentsAD23") (part "XT_CRYSTAL_12MHz_18pF"))
    )
  )
  (nets
    (net (code "1") (name "/BATT_LOW") (class "Default")
      (node (ref "R16") (pin "2") (pinfunction "2_2") (pintype "passive"))
      (node (ref "U1") (pin "4") (pinfunction "PB1/PWMH1/AD5_4") (pintype "bidirectional"))
    )
    (net (code "2") (name "/BATT_MEAS") (class "Default")
      (node (ref "R15") (pin "1") (pinfunction "1_1") (pintype "passive"))
      (node (ref "R17") (pin "1") (pinfunction "1_1") (pintype "passive"))
      (node (ref "U1") (pin "31") (pinfunction "PA8_31") (pintype "bidirectional"))
    )
    (net (code "3") (name "/Buzzer") (class "Default")
      (node (ref "R12") (pin "1") (pinfunction "1_1") (pintype "passive"))
      (node (ref "U1") (pin "44") (pinfunction "PWMH2/PA2_44") (pintype "bidirectional"))
    )
    (net (code "4") (name "/CE") (class "Default")
      (node (ref "U1") (pin "29") (pinfunction "PA10_29") (pintype "bidirectional"))
      (node (ref "U6") (pin "3") (pinfunction "CE_3") (pintype "passive"))
    )
    (net (code "5") (name "/CH_0") (class "Default")
      (node (ref "S3") (pin "1") (pinfunction "A1_1") (pintype "passive"))
      (node (ref "U1") (pin "26") (pinfunction "PA26_26") (pintype "bidirectional"))
    )
    (net (code "6") (name "/CH_1") (class "Default")
      (node (ref "S3") (pin "2") (pinfunction "A2_2") (pintype "passive"))
      (node (ref "U1") (pin "37") (pinfunction "PA27_37") (pintype "bidirectional"))
    )
    (net (code "7") (name "/CH_2") (class "Default")
      (node (ref "S3") (pin "3") (pinfunction "A3_3") (pintype "passive"))
      (node (ref "U1") (pin "38") (pinfunction "PA28_38") (pintype "bidirectional"))
    )
    (net (code "8") (name "/CH_3") (class "Default")
      (node (ref "S3") (pin "4") (pinfunction "A4_4") (pintype "passive"))
      (node (ref "U1") (pin "41") (pinfunction "PA29_41") (pintype "bidirectional"))
    )
    (net (code "9") (name "/CSN") (class "Default")
      (node (ref "TP25") (pin "1") (pinfunction "TP_1") (pintype "passive"))
      (node (ref "U1") (pin "28") (pinfunction "PWMH0/PA11_28") (pintype "bidirectional"))
      (node (ref "U6") (pin "4") (pinfunction "CSN_4") (pintype "passive"))
    )
    (net (code "10") (name "/D_N") (class "Default")
      (node (ref "H2") (pin "2") (pinfunction "D-_2") (pintype "bidirectional"))
      (node (ref "R5") (pin "1") (pinfunction "1_1") (pintype "passive"))
      (node (ref "TP10") (pin "1") (pinfunction "TP_1") (pintype "passive"))
    )
    (net (code "11") (name "/D_P") (class "Default")
      (node (ref "H2") (pin "3") (pinfunction "D+_3") (pintype "bidirectional"))
      (node (ref "R4") (pin "1") (pinfunction "1_1") (pintype "passive"))
      (node (ref "TP9") (pin "1") (pinfunction "TP_1") (pintype "passive"))
    )
    (net (code "12") (name "/INT1") (class "Default")
      (node (ref "TP20") (pin "1") (pinfunction "TP_1") (pintype "passive"))
      (node (ref "U1") (pin "48") (pinfunction "PWMH0/PA0_48") (pintype "bidirectional"))
      (node (ref "U5") (pin "8") (pinfunction "INT1_8") (pintype "output"))
    )
    (net (code "13") (name "/INT2") (class "Default")
      (node (ref "TP22") (pin "1") (pinfunction "TP_1") (pintype "passive"))
      (node (ref "U1") (pin "47") (pinfunction "PWMH1/PA1_47") (pintype "bidirectional"))
      (node (ref "U5") (pin "9") (pinfunction "INT2_9") (pintype "output"))
    )
    (net (code "14") (name "/IRQ") (class "Default")
      (node (ref "U1") (pin "23") (pinfunction "PWMH1/PA24_23") (pintype "bidirectional"))
      (node (ref "U6") (pin "8") (pinfunction "IRQ_8") (pintype "passive"))
    )
    (net (code "15") (name "/LED_IN") (class "Default")
      (node (ref "TP34") (pin "1") (pinfunction "TP_1") (pintype "passive"))
      (node (ref "U1") (pin "32") (pinfunction "PWMH3/PA7_32") (pintype "bidirectional"))
      (node (ref "U7") (pin "4") (pinfunction "B_4") (pintype "passive"))
    )
    (net (code "16") (name "/LED_OUT") (class "Default")
      (node (ref "H4") (pin "2") (pinfunction "DATA_2") (pintype "passive"))
      (node (ref "TP35") (pin "1") (pinfunction "TP_1") (pintype "passive"))
      (node (ref "U7") (pin "3") (pinfunction "A_3") (pintype "passive"))
    )
    (net (code "17") (name "/MISO") (class "Default")
      (node (ref "TP29") (pin "1") (pinfunction "TP_1") (pintype "passive"))
      (node (ref "U1") (pin "27") (pinfunction "MISO/PWMH1/PA12_27") (pintype "bidirectional"))
      (node (ref "U6") (pin "7") (pinfunction "MISO_7") (pintype "passive"))
    )
    (net (code "18") (name "/MOSI") (class "Default")
      (node (ref "TP27") (pin "1") (pinfunction "TP_1") (pintype "passive"))
      (node (ref "U1") (pin "22") (pinfunction "MOSI/PWMH2/PA13_22") (pintype "bidirectional"))
      (node (ref "U6") (pin "6") (pinfunction "MOSI_6") (pintype "passive"))
    )
    (net (code "19") (name "/SCL") (class "Default")
      (node (ref "R10") (pin "1") (pinfunction "1_1") (pintype "passive"))
      (node (ref "TP19") (pin "1") (pinfunction "TP_1") (pintype "passive"))
      (node (ref "U1") (pin "36") (pinfunction "TWCK0/PA4_36") (pintype "bidirectional"))
      (node (ref "U5") (pin "14") (pinfunction "SCL/SCLK_14") (pintype "input"))
    )
    (net (code "20") (name "/SCLK") (class "Default")
      (node (ref "TP26") (pin "1") (pinfunction "TP_1") (pintype "passive"))
      (node (ref "U1") (pin "21") (pinfunction "SPCK/PWMH3/PA14_21") (pintype "bidirectional"))
      (node (ref "U6") (pin "5") (pinfunction "SCK_5") (pintype "passive"))
    )
    (net (code "21") (name "/SDA") (class "Default")
      (node (ref "R9") (pin "1") (pinfunction "1_1") (pintype "passive"))
      (node (ref "TP21") (pin "1") (pinfunction "TP_1") (pintype "passive"))
      (node (ref "U1") (pin "43") (pinfunction "TWD0/PA3_43") (pintype "bidirectional"))
      (node (ref "U5") (pin "13") (pinfunction "SDA/SDI/SDIO_13") (pintype "bidirectional"))
    )
    (net (code "22") (name "/STAT0") (class "Default")
      (node (ref "R13") (pin "2") (pinfunction "2_2") (pintype "passive"))
      (node (ref "U1") (pin "16") (pinfunction "AD3/PWML1/PA20_16") (pintype "bidirectional"))
    )
    (net (code "23") (name "/STAT1") (class "Default")
      (node (ref "R14") (pin "2") (pinfunction "2_2") (pintype "passive"))
      (node (ref "U1") (pin "15") (pinfunction "PWMH0/PA23_15") (pintype "bidirectional"))
    )
    (net (code "24") (name "/SWCLK") (class "Default")
      (node (ref "H3") (pin "2") (pinfunction "2_2") (pintype "passive"))
      (node (ref "TP17") (pin "1") (pinfunction "TP_1") (pintype "passive"))
      (node (ref "U1") (pin "53") (pinfunction "PB7/SWCLK/TCK_53") (pintype "bidirectional"))
    )
    (net (code "25") (name "/SWDIO") (class "Default")
      (node (ref "H3") (pin "4") (pinfunction "4_4") (pintype "passive"))
      (node (ref "TP18") (pin "1") (pinfunction "TP_1") (pintype "passive"))
      (node (ref "U1") (pin "51") (pinfunction "PB6/SWDIO/TMS_51") (pintype "bidirectional"))
    )
    (net (code "26") (name "/nRST") (class "Default")
      (node (ref "H3") (pin "1") (pinfunction "1_1") (pintype "passive"))
      (node (ref "S1") (pin "2") (pintype "passive"))
      (node (ref "TP16") (pin "1") (pinfunction "TP_1") (pintype "passive"))
      (node (ref "U1") (pin "39") (pinfunction "~{NRST}_39") (pintype "bidirectional"))
    )
    (net (code "27") (name "3V3") (class "Default")
      (node (ref "C1") (pin "2") (pinfunction "2_2") (pintype "passive"))
      (node (ref "C11") (pin "2") (pinfunction "2_2") (pintype "passive"))
      (node (ref "C23") (pin "2") (pinfunction "2_2") (pintype "passive"))
      (node (ref "C24") (pin "2") (pinfunction "2_2") (pintype "passive"))
      (node (ref "C25") (pin "1") (pinfunction "1_1") (pintype "passive"))
      (node (ref "C27") (pin "2") (pinfunction "2_2") (pintype "passive"))
      (node (ref "C3") (pin "2") (pinfunction "2_2") (pintype "passive"))
      (node (ref "C5") (pin "2") (pinfunction "2_2") (pintype "passive"))
      (node (ref "C8") (pin "1") (pinfunction "1_1") (pintype "passive"))
      (node (ref "C9") (pin "2") (pinfunction "2_2") (pintype "passive"))
      (node (ref "DL1") (pin "2") (pinfunction "A_2") (pintype "passive"))
      (node (ref "DL2") (pin "2") (pinfunction "A_2") (pintype "passive"))
      (node (ref "DL3") (pin "2") (pinfunction "A_2") (pintype "passive"))
      (node (ref "H3") (pin "7") (pinfunction "7_7") (pintype "passive"))
      (node (ref "H3") (pin "8") (pinfunction "8_8") (pintype "passive"))
      (node (ref "P1") (pin "1") (pinfunction "1_1") (pintype "passive"))
      (node (ref "R10") (pin "2") (pinfunction "2_2") (pintype "passive"))
      (node (ref "R11") (pin "1") (pinfunction "1_1") (pintype "passive"))
      (node (ref "R9") (pin "2") (pinfunction "2_2") (pintype "passive"))
      (node (ref "TP1") (pin "1") (pinfunction "TP_1") (pintype "passive"))
      (node (ref "TP23") (pin "1") (pinfunction "TP_1") (pintype "passive"))
      (node (ref "TP3") (pin "1") (pinfunction "TP_1") (pintype "passive"))
      (node (ref "TP32") (pin "1") (pinfunction "TP_1") (pintype "passive"))
      (node (ref "TP7") (pin "1") (pinfunction "TP_1") (pintype "passive"))
      (node (ref "U1") (pin "1") (pinfunction "ADVREF_1") (pintype "input"))
      (node (ref "U1") (pin "18") (pinfunction "VDDIO_18") (pintype "power_in"))
      (node (ref "U1") (pin "45") (pinfunction "VDDIO_45") (pintype "power_in"))
      (node (ref "U1") (pin "58") (pinfunction "VDDIO_58") (pintype "power_in"))
      (node (ref "U1") (pin "7") (pinfunction "VDDIN_7") (pintype "power_in"))
      (node (ref "U2") (pin "5") (pinfunction "OUT_5") (pintype "power_in"))
      (node (ref "U5") (pin "1") (pinfunction "VDD_I/O_1") (pintype "power_in"))
      (node (ref "U5") (pin "6") (pinfunction "VS_6") (pintype "power_in"))
      (node (ref "U5") (pin "7") (pinfunction "~{CS}_7") (pintype "input"))
      (node (ref "U7") (pin "6") (pinfunction "VCCB_6") (pintype "passive"))
    )
    (net (code "28") (name "3V3RF") (class "Default")
      (node (ref "C15") (pin "1") (pinfunction "1_1") (pintype "passive"))
      (node (ref "L3") (pin "2") (pinfunction "2_2") (pintype "passive"))
      (node (ref "TP6") (pin "1") (pinfunction "TP_1") (pintype "passive"))
      (node (ref "U3") (pin "5") (pinfunction "OUT_5") (pintype "power_in"))
    )
    (net (code "29") (name "5V") (class "Default")
      (node (ref "C21") (pin "2") (pinfunction "2_2") (pintype "passive"))
      (node (ref "C22") (pin "2") (pinfunction "2_2") (pintype "passive"))
      (node (ref "C28") (pin "2") (pinfunction "2_2") (pintype "passive"))
      (node (ref "H4") (pin "1") (pinfunction "5V_1") (pintype "passive"))
      (node (ref "L2") (pin "2") (pintype "passive"))
      (node (ref "R1") (pin "1") (pinfunction "1_1") (pintype "passive"))
      (node (ref "R3") (pin "1") (pinfunction "1_1") (pintype "passive"))
      (node (ref "TP33") (pin "1") (pinfunction "TP_1") (pintype "passive"))
      (node (ref "U4") (pin "5") (pinfunction "FB_5") (pintype "input"))
      (node (ref "U7") (pin "1") (pinfunction "VCCA_1") (pintype "passive"))
    )
    (net (code "30") (name "GND") (class "Default")
      (node (ref "C1") (pin "1") (pinfunction "1_1") (pintype "passive"))
      (node (ref "C10") (pin "1") (pinfunction "1_1") (pintype "passive"))
      (node (ref "C11") (pin "1") (pinfunction "1_1") (pintype "passive"))
      (node (ref "C12") (pin "2") (pinfunction "2_2") (pintype "passive"))
      (node (ref "C14") (pin "2") (pinfunction "2_2") (pintype "passive"))
      (node (ref "C15") (pin "2") (pinfunction "2_2") (pintype "passive"))
      (node (ref "C16") (pin "2") (pinfunction "2_2") (pintype "passive"))
      (node (ref "C17") (pin "1") (pinfunction "1_1") (pintype "passive"))
      (node (ref "C18") (pin "1") (pinfunction "1_1") (pintype "passive"))
      (node (ref "C19") (pin "2") (pinfunction "2_2") (pintype "passive"))
      (node (ref "C2") (pin "1") (pinfunction "1_1") (pintype "passive"))
      (node (ref "C21") (pin "1") (pinfunction "1_1") (pintype "passive"))
      (node (ref "C22") (pin "1") (pinfunction "1_1") (pintype "passive"))
      (node (ref "C23") (pin "1") (pinfunction "1_1") (pintype "passive"))
      (node (ref "C24") (pin "1") (pinfunction "1_1") (pintype "passive"))
      (node (ref "C25") (pin "2") (pinfunction "2_2") (pintype "passive"))
      (node (ref "C26") (pin "2") (pinfunction "2_2") (pintype "passive"))
      (node (ref "C27") (pin "1") (pinfunction "1_1") (pintype "passive"))
      (node (ref "C28") (pin "1") (pinfunction "1_1") (pintype "passive"))
      (node (ref "C3") (pin "1") (pinfunction "1_1") (pintype "passive"))
      (node (ref "C4") (pin "1") (pinfunction "1_1") (pintype "passive"))
      (node (ref "C5") (pin "1") (pinfunction "1_1") (pintype "passive"))
      (node (ref "C6") (pin "1") (pinfunction "1_1") (pintype "passive"))
      (node (ref "C7") (pin "2") (pinfunction "2_2") (pintype "passive"))
      (node (ref "C8") (pin "2") (pinfunction "2_2") (pintype "passive"))
      (node (ref "C9") (pin "1") (pinfunction "1_1") (pintype "passive"))
      (node (ref "D1") (pin "1") (pinfunction "A_1") (pintype "passive"))
      (node (ref "H1") (pin "1") (pinfunction "GND_1") (pintype "passive"))
      (node (ref "H1") (pin "3") (pinfunction "GND_3") (pintype "passive"))
      (node (ref "H2") (pin "5") (pinfunction "GND_5") (pintype "passive"))
      (node (ref "H2") (pin "6") (pinfunction "SHLD_6") (pintype "passive"))
      (node (ref "H3") (pin "5") (pinfunction "5_5") (pintype "passive"))
      (node (ref "H3") (pin "6") (pinfunction "6_6") (pintype "passive"))
      (node (ref "H4") (pin "3") (pinfunction "COM_3") (pintype "passive"))
      (node (ref "Q1") (pin "1") (pinfunction "1_1") (pintype "passive"))
      (node (ref "Q2") (pin "2") (pinfunction "2_2") (pintype "passive"))
      (node (ref "R17") (pin "2") (pinfunction "2_2") (pintype "passive"))
      (node (ref "R2") (pin "2") (pinfunction "2_2") (pintype "passive"))
      (node (ref "R8") (pin "2") (pinfunction "2_2") (pintype "passive"))
      (node (ref "S1") (pin "1") (pintype "passive"))
      (node (ref "S2") (pin "1") (pintype "passive"))
      (node (ref "S3") (pin "5") (pinfunction "B4_5") (pintype "passive"))
      (node (ref "S3") (pin "6") (pinfunction "B3_6") (pintype "passive"))
      (node (ref "S3") (pin "7") (pinfunction "B2_7") (pintype "passive"))
      (node (ref "S3") (pin "8") (pinfunction "B1_8") (pintype "passive"))
      (node (ref "TP30") (pin "1") (pinfunction "TP_1") (pintype "passive"))
      (node (ref "TP31") (pin "1") (pinfunction "TP_1") (pintype "passive"))
      (node (ref "U1") (pin "17") (pinfunction "GND_17") (pintype "power_in"))
      (node (ref "U1") (pin "2") (pinfunction "GND_2") (pintype "power_in"))
      (node (ref "U1") (pin "46") (pinfunction "GND_46") (pintype "power_in"))
      (node (ref "U1") (pin "60") (pinfunction "GND_60") (pintype "power_in"))
      (node (ref "U2") (pin "2") (pinfunction "GND_2") (pintype "power_in"))
      (node (ref "U3") (pin "2") (pinfunction "GND_2") (pintype "power_in"))
      (node (ref "U4") (pin "7") (pinfunction "GND_7") (pintype "power_in"))
      (node (ref "U4") (pin "EPAD") (pinfunction "EPAD_EPAD") (pintype "passive"))
      (node (ref "U5") (pin "12") (pinfunction "SDO/ALT_ADDRESS_12") (pintype "bidirectional"))
      (node (ref "U5") (pin "2") (pinfunction "GND_2") (pintype "power_in"))
      (node (ref "U5") (pin "4") (pinfunction "GND_4") (pintype "power_in"))
      (node (ref "U5") (pin "5") (pinfunction "GND_5") (pintype "power_in"))
      (node (ref "U6") (pin "2") (pinfunction "GND_2") (pintype "passive"))
      (node (ref "U7") (pin "2") (pinfunction "GND_2") (pintype "passive"))
      (node (ref "U7") (pin "5") (pinfunction "DIR_5") (pintype "passive"))
    )
    (net (code "31") (name "Net-(C13-Pad2)") (class "Default")
      (node (ref "C13") (pin "2") (pinfunction "2_2") (pintype "passive"))
      (node (ref "R2") (pin "1") (pinfunction "1_1") (pintype "passive"))
    )
    (net (code "32") (name "Net-(D1-K)") (class "Default")
      (node (ref "C20") (pin "1") (pinfunction "1_1") (pintype "passive"))
      (node (ref "D1") (pin "2") (pinfunction "K_2") (pintype "passive"))
      (node (ref "L2") (pin "1") (pintype "passive"))
      (node (ref "U4") (pin "8") (pinfunction "SW_8") (pintype "output"))
    )
    (net (code "33") (name "Net-(DL1-K)") (class "Default")
      (node (ref "DL1") (pin "1") (pinfunction "K_1") (pintype "passive"))
      (node (ref "R13") (pin "1") (pinfunction "1_1") (pintype "passive"))
    )
    (net (code "34") (name "Net-(DL2-K)") (class "Default")
      (node (ref "DL2") (pin "1") (pinfunction "K_1") (pintype "passive"))
      (node (ref "R14") (pin "1") (pinfunction "1_1") (pintype "passive"))
    )
    (net (code "35") (name "Net-(DL3-K)") (class "Default")
      (node (ref "DL3") (pin "1") (pinfunction "K_1") (pintype "passive"))
      (node (ref "R16") (pin "1") (pinfunction "1_1") (pintype "passive"))
    )
    (net (code "36") (name "Net-(P1-Pad2)") (class "Default")
      (node (ref "P1") (pin "2") (pinfunction "2_2") (pintype "passive"))
      (node (ref "Q2") (pin "3") (pinfunction "3_3") (pintype "passive"))
      (node (ref "R11") (pin "2") (pinfunction "2_2") (pintype "passive"))
    )
    (net (code "37") (name "Net-(TP4-TP)") (class "Default")
      (node (ref "F1") (pin "2") (pinfunction "2_2") (pintype "passive"))
      (node (ref "Q1") (pin "3") (pinfunction "3_3") (pintype "passive"))
      (node (ref "TP4") (pin "1") (pinfunction "TP_1") (pintype "passive"))
    )
    (net (code "38") (name "Net-(TP5-TP)") (class "Default")
      (node (ref "C12") (pin "1") (pinfunction "1_1") (pintype "passive"))
      (node (ref "C13") (pin "1") (pinfunction "1_1") (pintype "passive"))
      (node (ref "L1") (pin "1") (pinfunction "1_1") (pintype "passive"))
      (node (ref "TP5") (pin "1") (pinfunction "TP_1") (pintype "passive"))
      (node (ref "U1") (pin "64") (pinfunction "VDDPLL_64") (pintype "power_in"))
    )
    (net (code "39") (name "Net-(TP8-TP)") (class "Default")
      (node (ref "TP8") (pin "1") (pinfunction "TP_1") (pintype "passive"))
      (node (ref "U1") (pin "55") (pinfunction "PB12/ERASE_55") (pintype "bidirectional"))
    )
    (net (code "40") (name "Net-(TP13-TP)") (class "Default")
      (node (ref "C17") (pin "2") (pinfunction "2_2") (pintype "passive"))
      (node (ref "TP13") (pin "1") (pinfunction "TP_1") (pintype "passive"))
      (node (ref "U1") (pin "62") (pinfunction "PB9/XIN_62") (pintype "bidirectional"))
      (node (ref "Y1") (pin "1") (pinfunction "OSC1_1") (pintype "passive"))
    )
    (net (code "41") (name "Net-(TP15-TP)") (class "Default")
      (node (ref "C20") (pin "2") (pinfunction "2_2") (pintype "passive"))
      (node (ref "TP15") (pin "1") (pinfunction "TP_1") (pintype "passive"))
      (node (ref "U4") (pin "1") (pinfunction "BST_1") (pintype "passive"))
    )
    (net (code "42") (name "Net-(TP24-TP)") (class "Default")
      (node (ref "C26") (pin "1") (pinfunction "1_1") (pintype "passive"))
      (node (ref "L3") (pin "1") (pinfunction "1_1") (pintype "passive"))
      (node (ref "TP24") (pin "1") (pinfunction "TP_1") (pintype "passive"))
      (node (ref "U6") (pin "1") (pinfunction "VCC_1") (pintype "passive"))
    )
    (net (code "43") (name "Net-(TP28-TP)") (class "Default")
      (node (ref "Q2") (pin "1") (pinfunction "1_1") (pintype "passive"))
      (node (ref "R12") (pin "2") (pinfunction "2_2") (pintype "passive"))
      (node (ref "TP28") (pin "1") (pinfunction "TP_1") (pintype "passive"))
    )
    (net (code "44") (name "Net-(U1A-PB8{slash}XOUT)") (class "Default")
      (node (ref "C18") (pin "2") (pinfunction "2_2") (pintype "passive"))
      (node (ref "U1") (pin "61") (pinfunction "PB8/XOUT_61") (pintype "bidirectional"))
      (node (ref "Y1") (pin "3") (pinfunction "OSC2_3") (pintype "passive"))
    )
    (net (code "45") (name "Net-(U1A-PB10{slash}DDM)") (class "Default")
      (node (ref "R5") (pin "2") (pinfunction "2_2") (pintype "passive"))
      (node (ref "U1") (pin "56") (pinfunction "PB10/DDM_56") (pintype "bidirectional"))
    )
    (net (code "46") (name "Net-(U1A-PB11{slash}DDP)") (class "Default")
      (node (ref "R4") (pin "2") (pinfunction "2_2") (pintype "passive"))
      (node (ref "U1") (pin "57") (pinfunction "PB11/DDP_57") (pintype "bidirectional"))
    )
    (net (code "47") (name "Net-(U1B-VDDOUT)") (class "Default")
      (node (ref "C10") (pin "2") (pinfunction "2_2") (pintype "passive"))
      (node (ref "C2") (pin "2") (pinfunction "2_2") (pintype "passive"))
      (node (ref "C4") (pin "2") (pinfunction "2_2") (pintype "passive"))
      (node (ref "C6") (pin "2") (pinfunction "2_2") (pintype "passive"))
      (node (ref "L1") (pin "2") (pinfunction "2_2") (pintype "passive"))
      (node (ref "U1") (pin "12") (pinfunction "VDDCORE_12") (pintype "power_in"))
      (node (ref "U1") (pin "24") (pinfunction "VDDCORE_24") (pintype "power_in"))
      (node (ref "U1") (pin "54") (pinfunction "VDDCORE_54") (pintype "power_in"))
      (node (ref "U1") (pin "8") (pinfunction "VDDOUT_8") (pintype "power_in"))
    )
    (net (code "48") (name "Net-(U2-EN)") (class "Default")
      (node (ref "C7") (pin "1") (pinfunction "1_1") (pintype "passive"))
      (node (ref "R1") (pin "2") (pinfunction "2_2") (pintype "passive"))
      (node (ref "U2") (pin "1") (pinfunction "IN_1") (pintype "power_in"))
      (node (ref "U2") (pin "3") (pinfunction "EN_3") (pintype "input"))
    )
    (net (code "49") (name "Net-(U3-EN)") (class "Default")
      (node (ref "C14") (pin "1") (pinfunction "1_1") (pintype "passive"))
      (node (ref "R3") (pin "2") (pinfunction "2_2") (pintype "passive"))
      (node (ref "U3") (pin "1") (pinfunction "IN_1") (pintype "power_in"))
      (node (ref "U3") (pin "3") (pinfunction "EN_3") (pintype "input"))
    )
    (net (code "50") (name "Net-(U4-PGOOD)") (class "Default")
      (node (ref "R7") (pin "2") (pinfunction "2_2") (pintype "passive"))
      (node (ref "U4") (pin "4") (pinfunction "PGOOD_4") (pintype "output"))
    )
    (net (code "51") (name "SLEEP") (class "Default")
      (node (ref "S2") (pin "2") (pintype "passive"))
      (node (ref "U1") (pin "49") (pinfunction "PB5/PWML0/TDO_49") (pintype "bidirectional"))
    )
    (net (code "52") (name "USB_DETECT") (class "Default")
      (node (ref "R6") (pin "2") (pinfunction "2_2") (pintype "passive"))
      (node (ref "R8") (pin "1") (pinfunction "1_1") (pintype "passive"))
      (node (ref "TP11") (pin "1") (pinfunction "TP_1") (pintype "passive"))
      (node (ref "U1") (pin "14") (pinfunction "AD9/TXD1/PA22_14") (pintype "bidirectional"))
    )
    (net (code "53") (name "VBUS") (class "Default")
      (node (ref "C16") (pin "1") (pinfunction "1_1") (pintype "passive"))
      (node (ref "H2") (pin "1") (pinfunction "VBUS_1") (pintype "power_in"))
      (node (ref "R6") (pin "1") (pinfunction "1_1") (pintype "passive"))
      (node (ref "TP12") (pin "1") (pinfunction "TP_1") (pintype "passive"))
    )
    (net (code "54") (name "V_BATT") (class "Default")
      (node (ref "C19") (pin "1") (pinfunction "1_1") (pintype "passive"))
      (node (ref "Q1") (pin "2") (pinfunction "2_2") (pintype "passive"))
      (node (ref "R15") (pin "2") (pinfunction "2_2") (pintype "passive"))
      (node (ref "R7") (pin "1") (pinfunction "1_1") (pintype "passive"))
      (node (ref "TP14") (pin "1") (pinfunction "TP_1") (pintype "passive"))
      (node (ref "U4") (pin "2") (pinfunction "VIN_2") (pintype "input"))
      (node (ref "U4") (pin "3") (pinfunction "EN_3") (pintype "input"))
    )
    (net (code "55") (name "V_BATT_RAW") (class "Default")
      (node (ref "F1") (pin "1") (pinfunction "1_1") (pintype "passive"))
      (node (ref "H1") (pin "2") (pinfunction "VBATT_2") (pintype "passive"))
    )
    (net (code "56") (name "unconnected-(H2-ID-Pad4)") (class "Default")
      (node (ref "H2") (pin "4") (pinfunction "ID_4") (pintype "power_in+no_connect"))
    )
    (net (code "57") (name "unconnected-(H3-Pad3)") (class "Default")
      (node (ref "H3") (pin "3") (pinfunction "3_3") (pintype "passive+no_connect"))
    )
    (net (code "58") (name "unconnected-(H3-Pad9)") (class "Default")
      (node (ref "H3") (pin "9") (pinfunction "9_9") (pintype "passive+no_connect"))
    )
    (net (code "59") (name "unconnected-(H3-Pad10)") (class "Default")
      (node (ref "H3") (pin "10") (pinfunction "10_10") (pintype "passive+no_connect"))
    )
    (net (code "60") (name "unconnected-(U1A-AD0{slash}PWMH3{slash}PA17-Pad9)") (class "Default")
      (node (ref "U1") (pin "9") (pinfunction "AD0/PWMH3/PA17_9") (pintype "bidirectional"))
    )
    (net (code "61") (name "unconnected-(U1A-AD1{slash}PA18-Pad10)") (class "Default")
      (node (ref "U1") (pin "10") (pinfunction "AD1/PA18_10") (pintype "bidirectional"))
    )
    (net (code "62") (name "unconnected-(U1A-AD2{slash}PWML0{slash}PA19-Pad13)") (class "Default")
      (node (ref "U1") (pin "13") (pinfunction "AD2/PWML0/PA19_13") (pintype "bidirectional"))
    )
    (net (code "63") (name "unconnected-(U1A-AD8{slash}RXD1{slash}PA21-Pad11)") (class "Default")
      (node (ref "U1") (pin "11") (pinfunction "AD8/RXD1/PA21_11") (pintype "bidirectional"))
    )
    (net (code "64") (name "unconnected-(U1A-JTAGSEL-Pad50)") (class "Default")
      (node (ref "U1") (pin "50") (pinfunction "JTAGSEL_50") (pintype "input+no_connect"))
    )
    (net (code "65") (name "unconnected-(U1A-PA9-Pad30)") (class "Default")
      (node (ref "U1") (pin "30") (pinfunction "PA9_30") (pintype "bidirectional"))
    )
    (net (code "66") (name "unconnected-(U1A-PA31-Pad52)") (class "Default")
      (node (ref "U1") (pin "52") (pinfunction "PA31_52") (pintype "bidirectional+no_connect"))
    )
    (net (code "67") (name "unconnected-(U1A-PB0{slash}PWMH0{slash}AD4-Pad3)") (class "Default")
      (node (ref "U1") (pin "3") (pinfunction "PB0/PWMH0/AD4_3") (pintype "bidirectional"))
    )
    (net (code "68") (name "unconnected-(U1A-PB2{slash}AD6-Pad5)") (class "Default")
      (node (ref "U1") (pin "5") (pinfunction "PB2/AD6_5") (pintype "bidirectional"))
    )
    (net (code "69") (name "unconnected-(U1A-PB3{slash}AD7-Pad6)") (class "Default")
      (node (ref "U1") (pin "6") (pinfunction "PB3/AD7_6") (pintype "bidirectional"))
    )
    (net (code "70") (name "unconnected-(U1A-PB4{slash}PWMH2{slash}TDI-Pad33)") (class "Default")
      (node (ref "U1") (pin "33") (pinfunction "PB4/PWMH2/TDI_33") (pintype "bidirectional"))
    )
    (net (code "71") (name "unconnected-(U1A-PB13{slash}PWML2{slash}DAC0-Pad59)") (class "Default")
      (node (ref "U1") (pin "59") (pinfunction "PB13/PWML2/DAC0_59") (pintype "bidirectional+no_connect"))
    )
    (net (code "72") (name "unconnected-(U1A-PB14{slash}PWMH3{slash}DAC1-Pad63)") (class "Default")
      (node (ref "U1") (pin "63") (pinfunction "PB14/PWMH3/DAC1_63") (pintype "bidirectional+no_connect"))
    )
    (net (code "73") (name "unconnected-(U1A-PWMH2{slash}PA25-Pad25)") (class "Default")
      (node (ref "U1") (pin "25") (pinfunction "PWMH2/PA25_25") (pintype "bidirectional"))
    )
    (net (code "74") (name "unconnected-(U1A-PWML2{slash}PA16-Pad19)") (class "Default")
      (node (ref "U1") (pin "19") (pinfunction "PWML2/PA16_19") (pintype "bidirectional"))
    )
    (net (code "75") (name "unconnected-(U1A-PWML2{slash}PA30-Pad42)") (class "Default")
      (node (ref "U1") (pin "42") (pinfunction "PWML2/PA30_42") (pintype "bidirectional"))
    )
    (net (code "76") (name "unconnected-(U1A-PWML3{slash}PA15-Pad20)") (class "Default")
      (node (ref "U1") (pin "20") (pinfunction "PWML3/PA15_20") (pintype "bidirectional"))
    )
    (net (code "77") (name "unconnected-(U1A-RXD0{slash}PA5-Pad35)") (class "Default")
      (node (ref "U1") (pin "35") (pinfunction "RXD0/PA5_35") (pintype "bidirectional"))
    )
    (net (code "78") (name "unconnected-(U1A-TST-Pad40)") (class "Default")
      (node (ref "U1") (pin "40") (pinfunction "TST_40") (pintype "input"))
    )
    (net (code "79") (name "unconnected-(U1A-TXD0{slash}PA6-Pad34)") (class "Default")
      (node (ref "U1") (pin "34") (pinfunction "TXD0/PA6_34") (pintype "bidirectional"))
    )
    (net (code "80") (name "unconnected-(U2-BYP-Pad4)") (class "Default")
      (node (ref "U2") (pin "4") (pinfunction "BYP_4") (pintype "passive+no_connect"))
    )
    (net (code "81") (name "unconnected-(U3-BYP-Pad4)") (class "Default")
      (node (ref "U3") (pin "4") (pinfunction "BYP_4") (pintype "passive+no_connect"))
    )
    (net (code "82") (name "unconnected-(U4-NC-Pad6)") (class "Default")
      (node (ref "U4") (pin "6") (pinfunction "NC_6") (pintype "passive+no_connect"))
    )
    (net (code "83") (name "unconnected-(U5-NC-Pad10)") (class "Default")
      (node (ref "U5") (pin "10") (pinfunction "NC_10") (pintype "passive+no_connect"))
    )
    (net (code "84") (name "unconnected-(U5-RESERVED-Pad3)") (class "Default")
      (node (ref "U5") (pin "3") (pinfunction "RESERVED_3") (pintype "passive+no_connect"))
    )
    (net (code "85") (name "unconnected-(U5-RESERVED-Pad11)") (class "Default")
      (node (ref "U5") (pin "11") (pinfunction "RESERVED_11") (pintype "passive+no_connect"))
    )
  )
)
